# 3-BitSelect.net
KiCad netlist of a schematic drawn in EAGLE
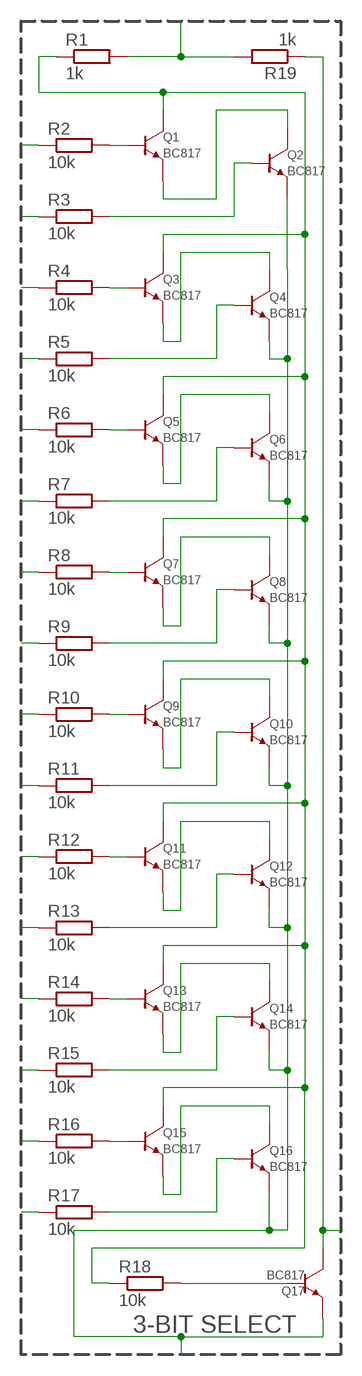
[diagram p0: schematic, sheet 1]

(export (version "E")
  (design (tool "Eeschema 10.0.6"))
  (components
    (comp (ref "Q1")
      (value "BC817")
      (footprint "eagle-import:SOT23")
      (libsource (lib "eagle-import") (part "TRANSISTOR-NPN-GENERIC-SOT23-BECDEFAULT"))
    )
    (comp (ref "Q2")
      (value "BC817")
      (footprint "eagle-import:SOT23")
      (libsource (lib "eagle-import") (part "TRANSISTOR-NPN-GENERIC-SOT23-BECDEFAULT"))
    )
    (comp (ref "Q3")
      (value "BC817")
      (footprint "eagle-import:SOT23")
      (libsource (lib "eagle-import") (part "TRANSISTOR-NPN-GENERIC-SOT23-BECDEFAULT"))
    )
    (comp (ref "Q4")
      (value "BC817")
      (footprint "eagle-import:SOT23")
      (libsource (lib "eagle-import") (part "TRANSISTOR-NPN-GENERIC-SOT23-BECDEFAULT"))
    )
    (comp (ref "Q5")
      (value "BC817")
      (footprint "eagle-import:SOT23")
      (libsource (lib "eagle-import") (part "TRANSISTOR-NPN-GENERIC-SOT23-BECDEFAULT"))
    )
    (comp (ref "Q6")
      (value "BC817")
      (footprint "eagle-import:SOT23")
      (libsource (lib "eagle-import") (part "TRANSISTOR-NPN-GENERIC-SOT23-BECDEFAULT"))
    )
    (comp (ref "Q7")
      (value "BC817")
      (footprint "eagle-import:SOT23")
      (libsource (lib "eagle-import") (part "TRANSISTOR-NPN-GENERIC-SOT23-BECDEFAULT"))
    )
    (comp (ref "Q8")
      (value "BC817")
      (footprint "eagle-import:SOT23")
      (libsource (lib "eagle-import") (part "TRANSISTOR-NPN-GENERIC-SOT23-BECDEFAULT"))
    )
    (comp (ref "Q9")
      (value "BC817")
      (footprint "eagle-import:SOT23")
      (libsource (lib "eagle-import") (part "TRANSISTOR-NPN-GENERIC-SOT23-BECDEFAULT"))
    )
    (comp (ref "Q10")
      (value "BC817")
      (footprint "eagle-import:SOT23")
      (libsource (lib "eagle-import") (part "TRANSISTOR-NPN-GENERIC-SOT23-BECDEFAULT"))
    )
    (comp (ref "Q11")
      (value "BC817")
      (footprint "eagle-import:SOT23")
      (libsource (lib "eagle-import") (part "TRANSISTOR-NPN-GENERIC-SOT23-BECDEFAULT"))
    )
    (comp (ref "Q12")
      (value "BC817")
      (footprint "eagle-import:SOT23")
      (libsource (lib "eagle-import") (part "TRANSISTOR-NPN-GENERIC-SOT23-BECDEFAULT"))
    )
    (comp (ref "Q13")
      (value "BC817")
      (footprint "eagle-import:SOT23")
      (libsource (lib "eagle-import") (part "TRANSISTOR-NPN-GENERIC-SOT23-BECDEFAULT"))
    )
    (comp (ref "Q14")
      (value "BC817")
      (footprint "eagle-import:SOT23")
      (libsource (lib "eagle-import") (part "TRANSISTOR-NPN-GENERIC-SOT23-BECDEFAULT"))
    )
    (comp (ref "Q15")
      (value "BC817")
      (footprint "eagle-import:SOT23")
      (libsource (lib "eagle-import") (part "TRANSISTOR-NPN-GENERIC-SOT23-BECDEFAULT"))
    )
    (comp (ref "Q16")
      (value "BC817")
      (footprint "eagle-import:SOT23")
      (libsource (lib "eagle-import") (part "TRANSISTOR-NPN-GENERIC-SOT23-BECDEFAULT"))
    )
    (comp (ref "Q17")
      (value "BC817")
      (footprint "eagle-import:SOT23")
      (libsource (lib "eagle-import") (part "TRANSISTOR-NPN-GENERIC-SOT23-BECDEFAULT"))
    )
    (comp (ref "R1")
      (value "1k")
      (footprint "eagle-import:R0603")
      (libsource (lib "eagle-import") (part "R-EU_R0603"))
    )
    (comp (ref "R2")
      (value "10k")
      (footprint "eagle-import:R0603")
      (libsource (lib "eagle-import") (part "R-EU_R0603"))
    )
    (comp (ref "R3")
      (value "10k")
      (footprint "eagle-import:R0603")
      (libsource (lib "eagle-import") (part "R-EU_R0603"))
    )
    (comp (ref "R4")
      (value "10k")
      (footprint "eagle-import:R0603")
      (libsource (lib "eagle-import") (part "R-EU_R0603"))
    )
    (comp (ref "R5")
      (value "10k")
      (footprint "eagle-import:R0603")
      (libsource (lib "eagle-import") (part "R-EU_R0603"))
    )
    (comp (ref "R6")
      (value "10k")
      (footprint "eagle-import:R0603")
      (libsource (lib "eagle-import") (part "R-EU_R0603"))
    )
    (comp (ref "R7")
      (value "10k")
      (footprint "eagle-import:R0603")
      (libsource (lib "eagle-import") (part "R-EU_R0603"))
    )
    (comp (ref "R8")
      (value "10k")
      (footprint "eagle-import:R0603")
      (libsource (lib "eagle-import") (part "R-EU_R0603"))
    )
    (comp (ref "R9")
      (value "10k")
      (footprint "eagle-import:R0603")
      (libsource (lib "eagle-import") (part "R-EU_R0603"))
    )
    (comp (ref "R10")
      (value "10k")
      (footprint "eagle-import:R0603")
      (libsource (lib "eagle-import") (part "R-EU_R0603"))
    )
    (comp (ref "R11")
      (value "10k")
      (footprint "eagle-import:R0603")
      (libsource (lib "eagle-import") (part "R-EU_R0603"))
    )
    (comp (ref "R12")
      (value "10k")
      (footprint "eagle-import:R0603")
      (libsource (lib "eagle-import") (part "R-EU_R0603"))
    )
    (comp (ref "R13")
      (value "10k")
      (footprint "eagle-import:R0603")
      (libsource (lib "eagle-import") (part "R-EU_R0603"))
    )
    (comp (ref "R14")
      (value "10k")
      (footprint "eagle-import:R0603")
      (libsource (lib "eagle-import") (part "R-EU_R0603"))
    )
    (comp (ref "R15")
      (value "10k")
      (footprint "eagle-import:R0603")
      (libsource (lib "eagle-import") (part "R-EU_R0603"))
    )
    (comp (ref "R16")
      (value "10k")
      (footprint "eagle-import:R0603")
      (libsource (lib "eagle-import") (part "R-EU_R0603"))
    )
    (comp (ref "R17")
      (value "10k")
      (footprint "eagle-import:R0603")
      (libsource (lib "eagle-import") (part "R-EU_R0603"))
    )
    (comp (ref "R18")
      (value "10k")
      (footprint "eagle-import:R0603")
      (libsource (lib "eagle-import") (part "R-EU_R0603"))
    )
    (comp (ref "R19")
      (value "1k")
      (footprint "eagle-import:R0603")
      (libsource (lib "eagle-import") (part "R-EU_R0603"))
    )
  )
  (nets
    (net (code "1") (name "Net-(Q1-BASE)") (class "Default")
      (node (ref "Q1") (pin "P$1") (pinfunction "BASE_P$1") (pintype "bidirectional"))
      (node (ref "R2") (pin "2") (pinfunction "2_2") (pintype "passive"))
    )
    (net (code "2") (name "Net-(Q1-COLLECTOR)") (class "Default")
      (node (ref "Q1") (pin "P$3") (pinfunction "COLLECTOR_P$3") (pintype "bidirectional"))
      (node (ref "Q11") (pin "P$3") (pinfunction "COLLECTOR_P$3") (pintype "bidirectional"))
      (node (ref "Q13") (pin "P$3") (pinfunction "COLLECTOR_P$3") (pintype "bidirectional"))
      (node (ref "Q15") (pin "P$3") (pinfunction "COLLECTOR_P$3") (pintype "bidirectional"))
      (node (ref "Q3") (pin "P$3") (pinfunction "COLLECTOR_P$3") (pintype "bidirectional"))
      (node (ref "Q5") (pin "P$3") (pinfunction "COLLECTOR_P$3") (pintype "bidirectional"))
      (node (ref "Q7") (pin "P$3") (pinfunction "COLLECTOR_P$3") (pintype "bidirectional"))
      (node (ref "Q9") (pin "P$3") (pinfunction "COLLECTOR_P$3") (pintype "bidirectional"))
      (node (ref "R1") (pin "1") (pinfunction "1_1") (pintype "passive"))
      (node (ref "R18") (pin "1") (pinfunction "1_1") (pintype "passive"))
    )
    (net (code "3") (name "Net-(Q1-EMITTER)") (class "Default")
      (node (ref "Q1") (pin "P$2") (pinfunction "EMITTER_P$2") (pintype "bidirectional"))
      (node (ref "Q2") (pin "P$3") (pinfunction "COLLECTOR_P$3") (pintype "bidirectional"))
    )
    (net (code "4") (name "Net-(Q2-BASE)") (class "Default")
      (node (ref "Q2") (pin "P$1") (pinfunction "BASE_P$1") (pintype "bidirectional"))
      (node (ref "R3") (pin "2") (pinfunction "2_2") (pintype "passive"))
    )
    (net (code "5") (name "Net-(Q3-BASE)") (class "Default")
      (node (ref "Q3") (pin "P$1") (pinfunction "BASE_P$1") (pintype "bidirectional"))
      (node (ref "R4") (pin "2") (pinfunction "2_2") (pintype "passive"))
    )
    (net (code "6") (name "Net-(Q3-EMITTER)") (class "Default")
      (node (ref "Q3") (pin "P$2") (pinfunction "EMITTER_P$2") (pintype "bidirectional"))
      (node (ref "Q4") (pin "P$3") (pinfunction "COLLECTOR_P$3") (pintype "bidirectional"))
    )
    (net (code "7") (name "Net-(Q4-BASE)") (class "Default")
      (node (ref "Q4") (pin "P$1") (pinfunction "BASE_P$1") (pintype "bidirectional"))
      (node (ref "R5") (pin "2") (pinfunction "2_2") (pintype "passive"))
    )
    (net (code "8") (name "Net-(Q5-BASE)") (class "Default")
      (node (ref "Q5") (pin "P$1") (pinfunction "BASE_P$1") (pintype "bidirectional"))
      (node (ref "R6") (pin "2") (pinfunction "2_2") (pintype "passive"))
    )
    (net (code "9") (name "Net-(Q5-EMITTER)") (class "Default")
      (node (ref "Q5") (pin "P$2") (pinfunction "EMITTER_P$2") (pintype "bidirectional"))
      (node (ref "Q6") (pin "P$3") (pinfunction "COLLECTOR_P$3") (pintype "bidirectional"))
    )
    (net (code "10") (name "Net-(Q6-BASE)") (class "Default")
      (node (ref "Q6") (pin "P$1") (pinfunction "BASE_P$1") (pintype "bidirectional"))
      (node (ref "R7") (pin "2") (pinfunction "2_2") (pintype "passive"))
    )
    (net (code "11") (name "Net-(Q7-BASE)") (class "Default")
      (node (ref "Q7") (pin "P$1") (pinfunction "BASE_P$1") (pintype "bidirectional"))
      (node (ref "R8") (pin "2") (pinfunction "2_2") (pintype "passive"))
    )
    (net (code "12") (name "Net-(Q7-EMITTER)") (class "Default")
      (node (ref "Q7") (pin "P$2") (pinfunction "EMITTER_P$2") (pintype "bidirectional"))
      (node (ref "Q8") (pin "P$3") (pinfunction "COLLECTOR_P$3") (pintype "bidirectional"))
    )
    (net (code "13") (name "Net-(Q8-BASE)") (class "Default")
      (node (ref "Q8") (pin "P$1") (pinfunction "BASE_P$1") (pintype "bidirectional"))
      (node (ref "R9") (pin "2") (pinfunction "2_2") (pintype "passive"))
    )
    (net (code "14") (name "Net-(Q9-BASE)") (class "Default")
      (node (ref "Q9") (pin "P$1") (pinfunction "BASE_P$1") (pintype "bidirectional"))
      (node (ref "R10") (pin "2") (pinfunction "2_2") (pintype "passive"))
    )
    (net (code "15") (name "Net-(Q10-BASE)") (class "Default")
      (node (ref "Q10") (pin "P$1") (pinfunction "BASE_P$1") (pintype "bidirectional"))
      (node (ref "R11") (pin "2") (pinfunction "2_2") (pintype "passive"))
    )
    (net (code "16") (name "Net-(Q10-COLLECTOR)") (class "Default")
      (node (ref "Q10") (pin "P$3") (pinfunction "COLLECTOR_P$3") (pintype "bidirectional"))
      (node (ref "Q9") (pin "P$2") (pinfunction "EMITTER_P$2") (pintype "bidirectional"))
    )
    (net (code "17") (name "Net-(Q10-EMITTER)") (class "Default")
      (node (ref "Q10") (pin "P$2") (pinfunction "EMITTER_P$2") (pintype "bidirectional"))
      (node (ref "Q12") (pin "P$2") (pinfunction "EMITTER_P$2") (pintype "bidirectional"))
      (node (ref "Q14") (pin "P$2") (pinfunction "EMITTER_P$2") (pintype "bidirectional"))
      (node (ref "Q16") (pin "P$2") (pinfunction "EMITTER_P$2") (pintype "bidirectional"))
      (node (ref "Q17") (pin "P$2") (pinfunction "EMITTER_P$2") (pintype "bidirectional"))
      (node (ref "Q2") (pin "P$2") (pinfunction "EMITTER_P$2") (pintype "bidirectional"))
      (node (ref "Q4") (pin "P$2") (pinfunction "EMITTER_P$2") (pintype "bidirectional"))
      (node (ref "Q6") (pin "P$2") (pinfunction "EMITTER_P$2") (pintype "bidirectional"))
      (node (ref "Q8") (pin "P$2") (pinfunction "EMITTER_P$2") (pintype "bidirectional"))
    )
    (net (code "18") (name "Net-(Q11-BASE)") (class "Default")
      (node (ref "Q11") (pin "P$1") (pinfunction "BASE_P$1") (pintype "bidirectional"))
      (node (ref "R12") (pin "2") (pinfunction "2_2") (pintype "passive"))
    )
    (net (code "19") (name "Net-(Q11-EMITTER)") (class "Default")
      (node (ref "Q11") (pin "P$2") (pinfunction "EMITTER_P$2") (pintype "bidirectional"))
      (node (ref "Q12") (pin "P$3") (pinfunction "COLLECTOR_P$3") (pintype "bidirectional"))
    )
    (net (code "20") (name "Net-(Q12-BASE)") (class "Default")
      (node (ref "Q12") (pin "P$1") (pinfunction "BASE_P$1") (pintype "bidirectional"))
      (node (ref "R13") (pin "2") (pinfunction "2_2") (pintype "passive"))
    )
    (net (code "21") (name "Net-(Q13-BASE)") (class "Default")
      (node (ref "Q13") (pin "P$1") (pinfunction "BASE_P$1") (pintype "bidirectional"))
      (node (ref "R14") (pin "2") (pinfunction "2_2") (pintype "passive"))
    )
    (net (code "22") (name "Net-(Q13-EMITTER)") (class "Default")
      (node (ref "Q13") (pin "P$2") (pinfunction "EMITTER_P$2") (pintype "bidirectional"))
      (node (ref "Q14") (pin "P$3") (pinfunction "COLLECTOR_P$3") (pintype "bidirectional"))
    )
    (net (code "23") (name "Net-(Q14-BASE)") (class "Default")
      (node (ref "Q14") (pin "P$1") (pinfunction "BASE_P$1") (pintype "bidirectional"))
      (node (ref "R15") (pin "2") (pinfunction "2_2") (pintype "passive"))
    )
    (net (code "24") (name "Net-(Q15-BASE)") (class "Default")
      (node (ref "Q15") (pin "P$1") (pinfunction "BASE_P$1") (pintype "bidirectional"))
      (node (ref "R16") (pin "2") (pinfunction "2_2") (pintype "passive"))
    )
    (net (code "25") (name "Net-(Q15-EMITTER)") (class "Default")
      (node (ref "Q15") (pin "P$2") (pinfunction "EMITTER_P$2") (pintype "bidirectional"))
      (node (ref "Q16") (pin "P$3") (pinfunction "COLLECTOR_P$3") (pintype "bidirectional"))
    )
    (net (code "26") (name "Net-(Q16-BASE)") (class "Default")
      (node (ref "Q16") (pin "P$1") (pinfunction "BASE_P$1") (pintype "bidirectional"))
      (node (ref "R17") (pin "2") (pinfunction "2_2") (pintype "passive"))
    )
    (net (code "27") (name "Net-(Q17-BASE)") (class "Default")
      (node (ref "Q17") (pin "P$1") (pinfunction "BASE_P$1") (pintype "bidirectional"))
      (node (ref "R18") (pin "2") (pinfunction "2_2") (pintype "passive"))
    )
    (net (code "28") (name "Net-(Q17-COLLECTOR)") (class "Default")
      (node (ref "Q17") (pin "P$3") (pinfunction "COLLECTOR_P$3") (pintype "bidirectional"))
      (node (ref "R19") (pin "1") (pinfunction "1_1") (pintype "passive"))
    )
    (net (code "29") (name "Net-(R1-Pad2)") (class "Default")
      (node (ref "R1") (pin "2") (pinfunction "2_2") (pintype "passive"))
      (node (ref "R19") (pin "2") (pinfunction "2_2") (pintype "passive"))
    )
    (net (code "30") (name "unconnected-(R2-Pad1)") (class "Default")
      (node (ref "R2") (pin "1") (pinfunction "1_1") (pintype "passive"))
    )
    (net (code "31") (name "unconnected-(R3-Pad1)") (class "Default")
      (node (ref "R3") (pin "1") (pinfunction "1_1") (pintype "passive"))
    )
    (net (code "32") (name "unconnected-(R4-Pad1)") (class "Default")
      (node (ref "R4") (pin "1") (pinfunction "1_1") (pintype "passive"))
    )
    (net (code "33") (name "unconnected-(R5-Pad1)") (class "Default")
      (node (ref "R5") (pin "1") (pinfunction "1_1") (pintype "passive"))
    )
    (net (code "34") (name "unconnected-(R6-Pad1)") (class "Default")
      (node (ref "R6") (pin "1") (pinfunction "1_1") (pintype "passive"))
    )
    (net (code "35") (name "unconnected-(R7-Pad1)") (class "Default")
      (node (ref "R7") (pin "1") (pinfunction "1_1") (pintype "passive"))
    )
    (net (code "36") (name "unconnected-(R8-Pad1)") (class "Default")
      (node (ref "R8") (pin "1") (pinfunction "1_1") (pintype "passive"))
    )
    (net (code "37") (name "unconnected-(R9-Pad1)") (class "Default")
      (node (ref "R9") (pin "1") (pinfunction "1_1") (pintype "passive"))
    )
    (net (code "38") (name "unconnected-(R10-Pad1)") (class "Default")
      (node (ref "R10") (pin "1") (pinfunction "1_1") (pintype "passive"))
    )
    (net (code "39") (name "unconnected-(R11-Pad1)") (class "Default")
      (node (ref "R11") (pin "1") (pinfunction "1_1") (pintype "passive"))
    )
    (net (code "40") (name "unconnected-(R12-Pad1)") (class "Default")
      (node (ref "R12") (pin "1") (pinfunction "1_1") (pintype "passive"))
    )
    (net (code "41") (name "unconnected-(R13-Pad1)") (class "Default")
      (node (ref "R13") (pin "1") (pinfunction "1_1") (pintype "passive"))
    )
    (net (code "42") (name "unconnected-(R14-Pad1)") (class "Default")
      (node (ref "R14") (pin "1") (pinfunction "1_1") (pintype "passive"))
    )
    (net (code "43") (name "unconnected-(R15-Pad1)") (class "Default")
      (node (ref "R15") (pin "1") (pinfunction "1_1") (pintype "passive"))
    )
    (net (code "44") (name "unconnected-(R16-Pad1)") (class "Default")
      (node (ref "R16") (pin "1") (pinfunction "1_1") (pintype "passive"))
    )
    (net (code "45") (name "unconnected-(R17-Pad1)") (class "Default")
      (node (ref "R17") (pin "1") (pinfunction "1_1") (pintype "passive"))
    )
  )
)
